# IPG_Sensor_V2.net
KiCad netlist of a schematic drawn in EasyEDA
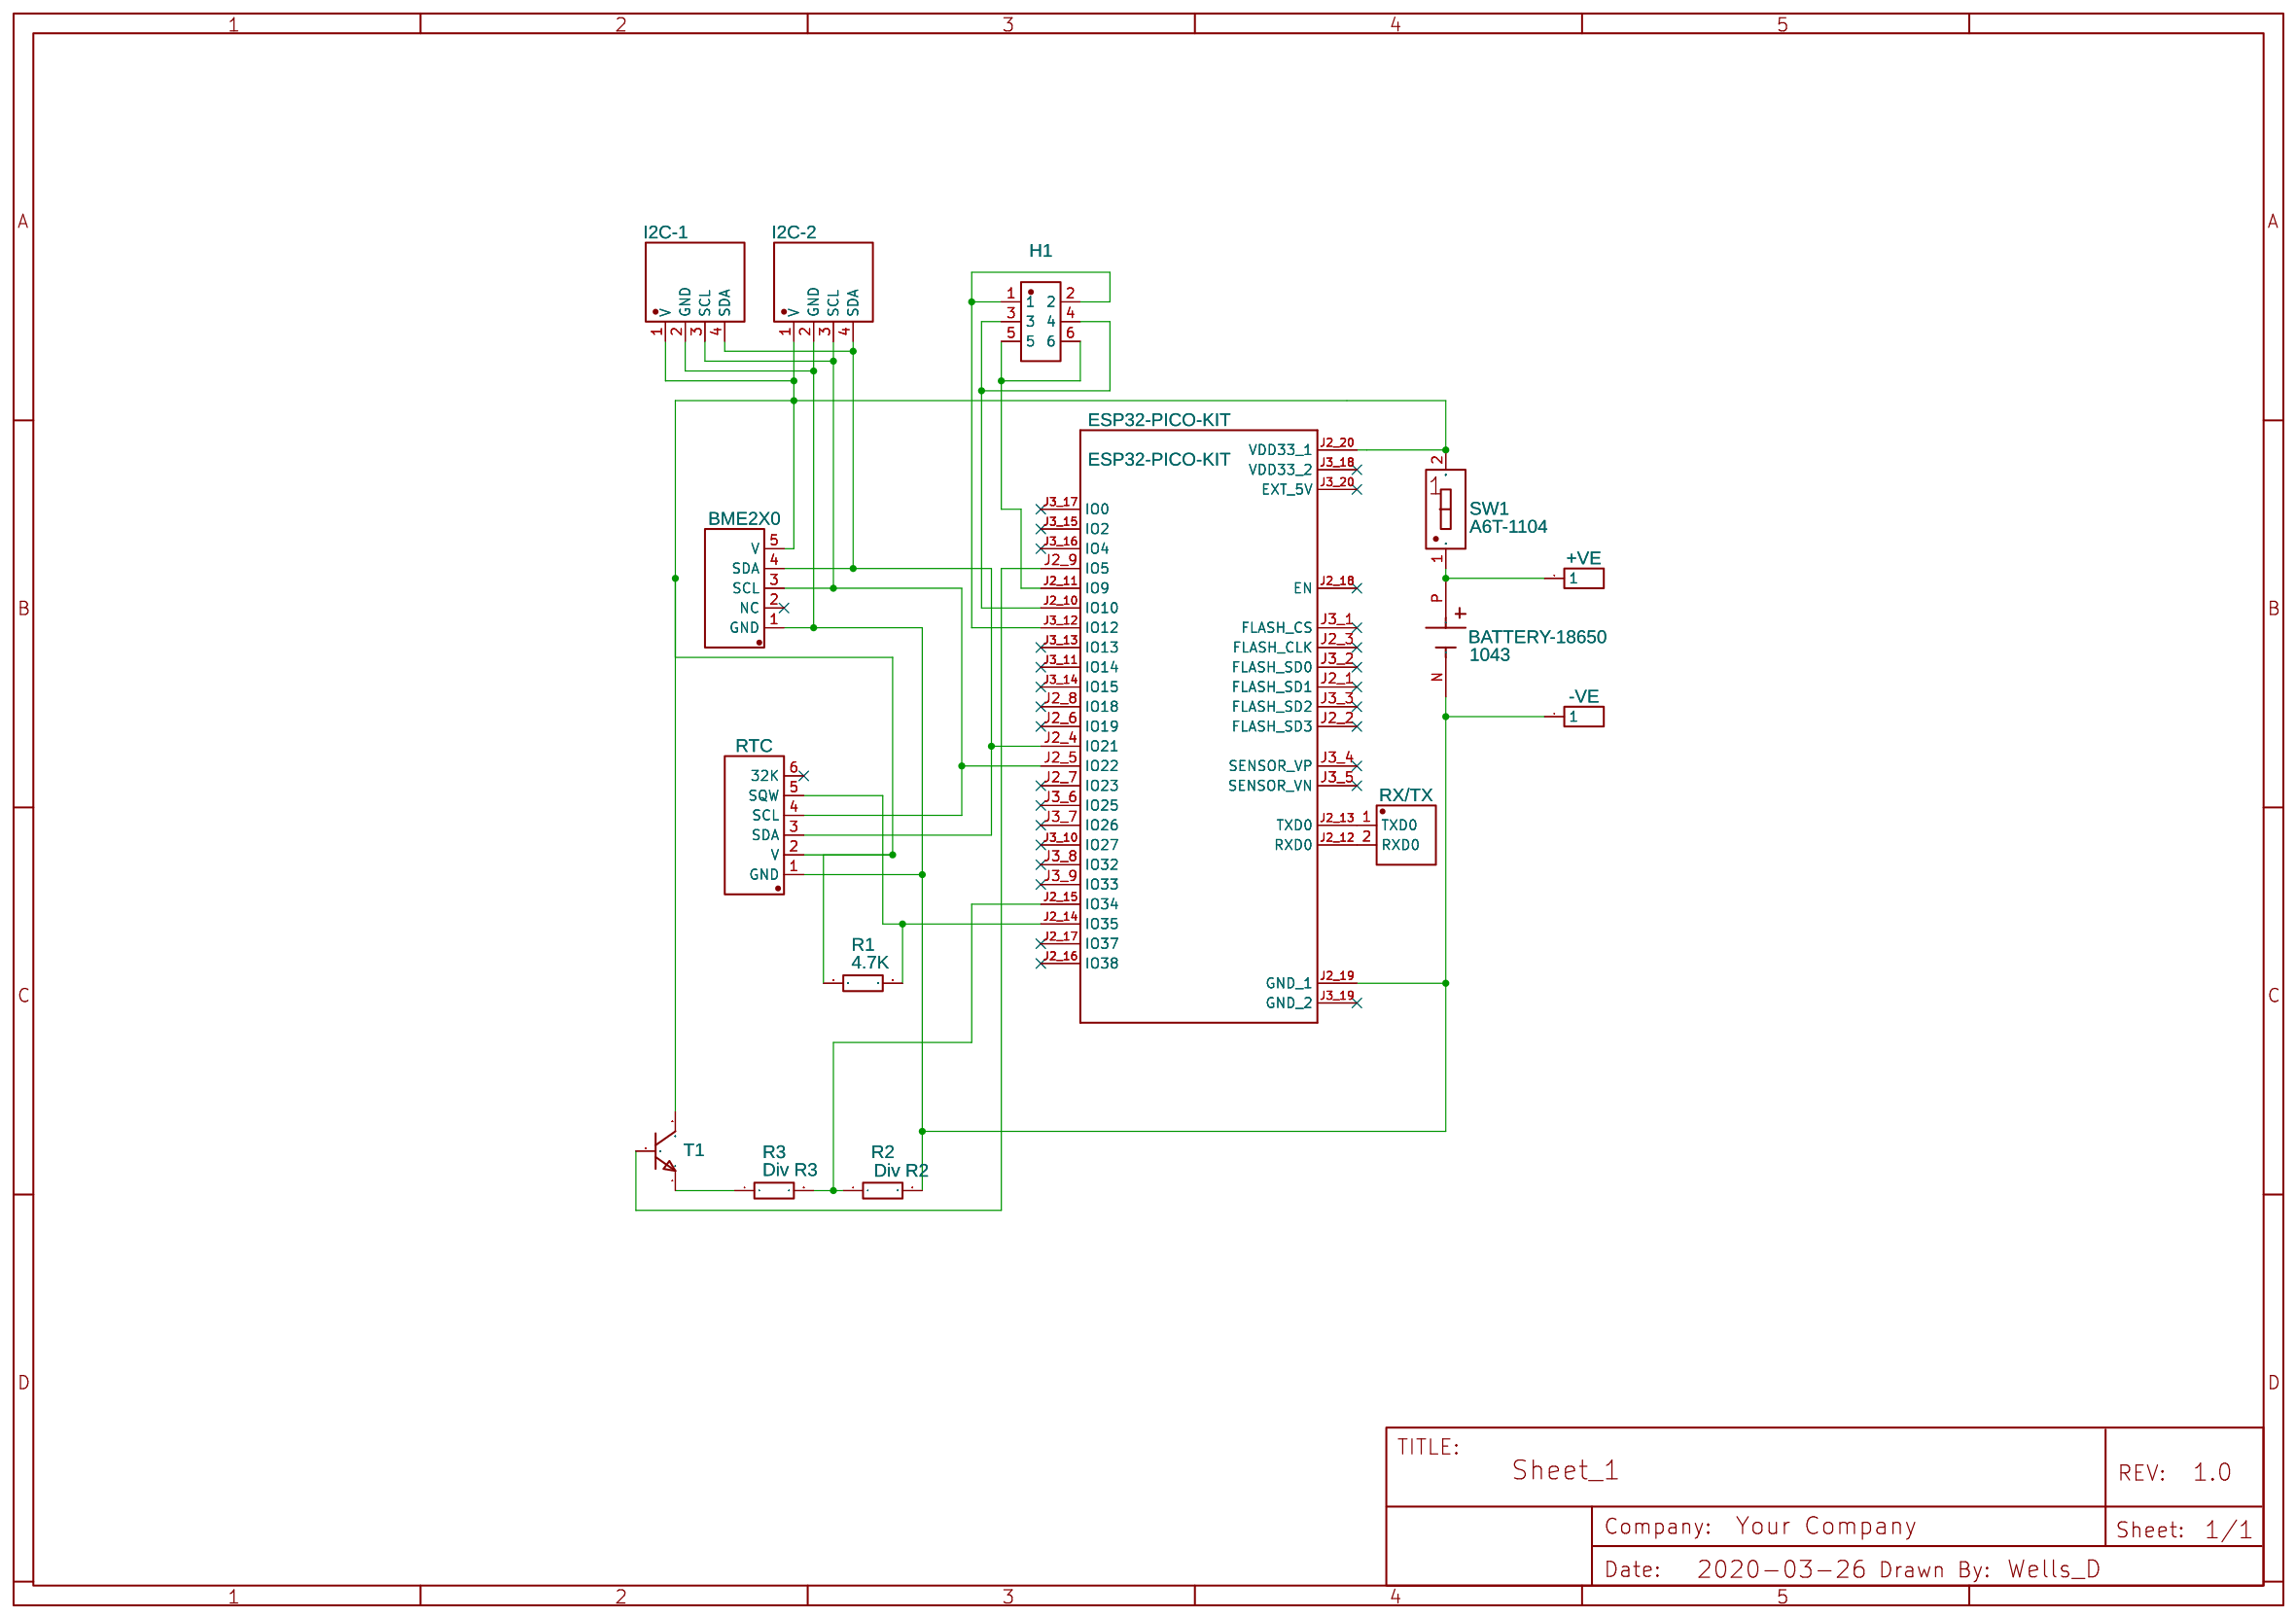
[diagram p0: schematic sheet]

(export (version "E")
  (design (tool "Eeschema 10.0.6"))
  (components
    (comp (ref "+VE")
      (value "Header-Male-2.54_1x1")
      (fields (field (name "BOM_Supplier Part") "C81276"))
      (libsource (lib "") (part "Header-Male-2.54_1x1"))
    )
    (comp (ref "-VE")
      (value "Header-Male-2.54_1x1")
      (fields (field (name "BOM_Supplier Part") "C81276"))
      (libsource (lib "") (part "Header-Male-2.54_1x1_1"))
    )
    (comp (ref "BATTERY-18650") (value "1043") (libsource (lib "") (part "1043")))
    (comp (ref "BME2X0")
      (value "2685Y-105CNG1SNA01")
      (fields (field (name "BOM_Supplier Part") "C350302"))
      (libsource (lib "") (part "2685Y-105CNG1SNA01"))
    )
    (comp (ref "ESP32-PICO-KIT") (value "ESP32-PICO-KIT") (libsource (lib "") (part "ESP32-PICO-KIT")))
    (comp (ref "H1")
      (value "67997-206HLF")
      (fields (field (name "BOM_Supplier Part") "C236051"))
      (libsource (lib "") (part "67997-206HLF"))
    )
    (comp (ref "I2C-1")
      (value "1")
      (fields (field (name "BOM_Supplier Part") "C160334"))
      (libsource (lib "") (part "RE-H042TD-1190 (LF)(SN)"))
    )
    (comp (ref "I2C-2")
      (value "2")
      (fields (field (name "BOM_Supplier Part") "C160334"))
      (libsource (lib "") (part "RE-H042TD-1190 (LF)(SN)"))
    )
    (comp (ref "R1")
      (value "4.7K")
      (fields
        (field (name "BOM_Manufacturer Part") "RN1/2W4.7KΩFT/BA1")
        (field (name "BOM_Supplier Part") "C385631")
      )
      (libsource (lib "") (part "RN1/2W4.7KΩFT/BA1"))
    )
    (comp (ref "R2")
      (value "Div R2")
      (fields
        (field (name "BOM_Manufacturer Part") "RN1/2W4.7KΩFT/BA1")
        (field (name "BOM_Supplier Part") "C385631")
      )
      (libsource (lib "") (part "RN1/2W4.7KΩFT/BA1"))
    )
    (comp (ref "R3")
      (value "Div R3")
      (fields
        (field (name "BOM_Manufacturer Part") "RN1/2W4.7KΩFT/BA1")
        (field (name "BOM_Supplier Part") "C385631")
      )
      (libsource (lib "") (part "RN1/2W4.7KΩFT/BA1"))
    )
    (comp (ref "RTC")
      (value "68000-406HLF")
      (fields (field (name "BOM_Supplier Part") "C178289"))
      (libsource (lib "") (part "68000-406HLF"))
    )
    (comp (ref "RX/TX")
      (value "RE-H022TD-1190 (LF)(SN)")
      (fields (field (name "BOM_Supplier Part") "C160332"))
      (libsource (lib "") (part "RE-H022TD-1190 (LF)(SN)"))
    )
    (comp (ref "SW1")
      (value "A6T-1104")
      (fields (field (name "BOM_Supplier Part") "C306874"))
      (libsource (lib "") (part "A6T-1104"))
    )
    (comp (ref "T1")
      (value "2N2222")
      (fields (field (name "BOM_Supplier Part") "C118536"))
      (libsource (lib "") (part "2N2222"))
    )
  )
  (nets
    (net (code "1") (name "Net-(BME2X0-GND)") (class "Default")
      (node (ref "-VE") (pin "1") (pinfunction "1_1") (pintype "input"))
      (node (ref "BATTERY-18650") (pin "N") (pinfunction "N_N") (pintype "unspecified"))
      (node (ref "BME2X0") (pin "1") (pinfunction "GND_1") (pintype "unspecified"))
      (node (ref "ESP32-PICO-KIT") (pin "J2_19") (pinfunction "GND_1_J2_19") (pintype "bidirectional"))
      (node (ref "I2C-1") (pin "2") (pinfunction "GND_2") (pintype "unspecified"))
      (node (ref "I2C-2") (pin "2") (pinfunction "GND_2") (pintype "unspecified"))
      (node (ref "R2") (pin "2") (pinfunction "2_2") (pintype "unspecified"))
      (node (ref "RTC") (pin "1") (pinfunction "GND_1") (pintype "unspecified"))
    )
    (net (code "2") (name "Net-(BME2X0-SCL)") (class "Default")
      (node (ref "BME2X0") (pin "3") (pinfunction "SCL_3") (pintype "unspecified"))
      (node (ref "ESP32-PICO-KIT") (pin "J2_5") (pinfunction "IO22_J2_5") (pintype "bidirectional"))
      (node (ref "I2C-1") (pin "3") (pinfunction "SCL_3") (pintype "unspecified"))
      (node (ref "I2C-2") (pin "3") (pinfunction "SCL_3") (pintype "unspecified"))
      (node (ref "RTC") (pin "4") (pinfunction "SCL_4") (pintype "unspecified"))
    )
    (net (code "3") (name "Net-(BME2X0-SDA)") (class "Default")
      (node (ref "BME2X0") (pin "4") (pinfunction "SDA_4") (pintype "unspecified"))
      (node (ref "ESP32-PICO-KIT") (pin "J2_4") (pinfunction "IO21_J2_4") (pintype "bidirectional"))
      (node (ref "I2C-1") (pin "4") (pinfunction "SDA_4") (pintype "unspecified"))
      (node (ref "I2C-2") (pin "4") (pinfunction "SDA_4") (pintype "unspecified"))
      (node (ref "RTC") (pin "3") (pinfunction "SDA_3") (pintype "unspecified"))
    )
    (net (code "4") (name "Net-(BME2X0-V)") (class "Default")
      (node (ref "BME2X0") (pin "5") (pinfunction "V_5") (pintype "unspecified"))
      (node (ref "ESP32-PICO-KIT") (pin "J2_20") (pinfunction "VDD33_1_J2_20") (pintype "bidirectional"))
      (node (ref "I2C-1") (pin "1") (pinfunction "V_1") (pintype "unspecified"))
      (node (ref "I2C-2") (pin "1") (pinfunction "V_1") (pintype "unspecified"))
      (node (ref "R1") (pin "1") (pinfunction "1_1") (pintype "unspecified"))
      (node (ref "RTC") (pin "2") (pinfunction "V_2") (pintype "unspecified"))
      (node (ref "SW1") (pin "2") (pinfunction "PIN2_2") (pintype "unspecified"))
      (node (ref "T1") (pin "3") (pinfunction "C_3") (pintype "unspecified"))
    )
    (net (code "5") (name "Net-(ESP32-PICO-KIT-IO5)") (class "Default")
      (node (ref "ESP32-PICO-KIT") (pin "J2_9") (pinfunction "IO5_J2_9") (pintype "bidirectional"))
      (node (ref "T1") (pin "2") (pinfunction "B_2") (pintype "unspecified"))
    )
    (net (code "6") (name "Net-(ESP32-PICO-KIT-IO9)") (class "Default")
      (node (ref "ESP32-PICO-KIT") (pin "J2_11") (pinfunction "IO9_J2_11") (pintype "bidirectional"))
      (node (ref "H1") (pin "5") (pinfunction "5_5") (pintype "unspecified"))
      (node (ref "H1") (pin "6") (pinfunction "6_6") (pintype "unspecified"))
    )
    (net (code "7") (name "Net-(ESP32-PICO-KIT-IO10)") (class "Default")
      (node (ref "ESP32-PICO-KIT") (pin "J2_10") (pinfunction "IO10_J2_10") (pintype "bidirectional"))
      (node (ref "H1") (pin "3") (pinfunction "3_3") (pintype "unspecified"))
      (node (ref "H1") (pin "4") (pinfunction "4_4") (pintype "unspecified"))
    )
    (net (code "8") (name "Net-(ESP32-PICO-KIT-IO12)") (class "Default")
      (node (ref "ESP32-PICO-KIT") (pin "J3_12") (pinfunction "IO12_J3_12") (pintype "bidirectional"))
      (node (ref "H1") (pin "1") (pinfunction "1_1") (pintype "unspecified"))
      (node (ref "H1") (pin "2") (pinfunction "2_2") (pintype "unspecified"))
    )
    (net (code "9") (name "Net-(ESP32-PICO-KIT-IO34)") (class "Default")
      (node (ref "ESP32-PICO-KIT") (pin "J2_15") (pinfunction "IO34_J2_15") (pintype "input"))
      (node (ref "R2") (pin "1") (pinfunction "1_1") (pintype "unspecified"))
      (node (ref "R3") (pin "2") (pinfunction "2_2") (pintype "unspecified"))
    )
    (net (code "10") (name "Net-(ESP32-PICO-KIT-IO35)") (class "Default")
      (node (ref "ESP32-PICO-KIT") (pin "J2_14") (pinfunction "IO35_J2_14") (pintype "input"))
      (node (ref "R1") (pin "2") (pinfunction "2_2") (pintype "unspecified"))
      (node (ref "RTC") (pin "5") (pinfunction "SQW_5") (pintype "unspecified"))
    )
    (net (code "11") (name "Net-(ESP32-PICO-KIT-RXD0)") (class "Default")
      (node (ref "ESP32-PICO-KIT") (pin "J2_12") (pinfunction "RXD0_J2_12") (pintype "bidirectional"))
      (node (ref "RX/TX") (pin "2") (pinfunction "RXD0_2") (pintype "unspecified"))
    )
    (net (code "12") (name "Net-(ESP32-PICO-KIT-TXD0)") (class "Default")
      (node (ref "ESP32-PICO-KIT") (pin "J2_13") (pinfunction "TXD0_J2_13") (pintype "bidirectional"))
      (node (ref "RX/TX") (pin "1") (pinfunction "TXD0_1") (pintype "unspecified"))
    )
    (net (code "13") (name "Net-(SW1-PIN1)") (class "Default")
      (node (ref "+VE") (pin "1") (pinfunction "1_1") (pintype "input"))
      (node (ref "BATTERY-18650") (pin "P") (pinfunction "P_P") (pintype "unspecified"))
      (node (ref "SW1") (pin "1") (pinfunction "PIN1_1") (pintype "unspecified"))
    )
    (net (code "14") (name "Net-(T1-E)") (class "Default")
      (node (ref "R3") (pin "1") (pinfunction "1_1") (pintype "unspecified"))
      (node (ref "T1") (pin "1") (pinfunction "E_1") (pintype "unspecified"))
    )
    (net (code "15") (name "unconnected-(BME2X0-NC-Pad2)") (class "Default")
      (node (ref "BME2X0") (pin "2") (pinfunction "NC_2") (pintype "unspecified+no_connect"))
    )
    (net (code "16") (name "unconnected-(ESP32-PICO-KIT-EN-PadJ2_18)") (class "Default")
      (node (ref "ESP32-PICO-KIT") (pin "J2_18") (pinfunction "EN_J2_18") (pintype "input+no_connect"))
    )
    (net (code "17") (name "unconnected-(ESP32-PICO-KIT-EXT_5V-PadJ3_20)") (class "Default")
      (node (ref "ESP32-PICO-KIT") (pin "J3_20") (pinfunction "EXT_5V_J3_20") (pintype "bidirectional+no_connect"))
    )
    (net (code "18") (name "unconnected-(ESP32-PICO-KIT-FLASH_CLK-PadJ2_3)") (class "Default")
      (node (ref "ESP32-PICO-KIT") (pin "J2_3") (pinfunction "FLASH_CLK_J2_3") (pintype "bidirectional+no_connect"))
    )
    (net (code "19") (name "unconnected-(ESP32-PICO-KIT-FLASH_CS-PadJ3_1)") (class "Default")
      (node (ref "ESP32-PICO-KIT") (pin "J3_1") (pinfunction "FLASH_CS_J3_1") (pintype "bidirectional+no_connect"))
    )
    (net (code "20") (name "unconnected-(ESP32-PICO-KIT-FLASH_SD0-PadJ3_2)") (class "Default")
      (node (ref "ESP32-PICO-KIT") (pin "J3_2") (pinfunction "FLASH_SD0_J3_2") (pintype "bidirectional+no_connect"))
    )
    (net (code "21") (name "unconnected-(ESP32-PICO-KIT-FLASH_SD1-PadJ2_1)") (class "Default")
      (node (ref "ESP32-PICO-KIT") (pin "J2_1") (pinfunction "FLASH_SD1_J2_1") (pintype "bidirectional+no_connect"))
    )
    (net (code "22") (name "unconnected-(ESP32-PICO-KIT-FLASH_SD2-PadJ3_3)") (class "Default")
      (node (ref "ESP32-PICO-KIT") (pin "J3_3") (pinfunction "FLASH_SD2_J3_3") (pintype "bidirectional+no_connect"))
    )
    (net (code "23") (name "unconnected-(ESP32-PICO-KIT-FLASH_SD3-PadJ2_2)") (class "Default")
      (node (ref "ESP32-PICO-KIT") (pin "J2_2") (pinfunction "FLASH_SD3_J2_2") (pintype "bidirectional+no_connect"))
    )
    (net (code "24") (name "unconnected-(ESP32-PICO-KIT-GND_2-PadJ3_19)") (class "Default")
      (node (ref "ESP32-PICO-KIT") (pin "J3_19") (pinfunction "GND_2_J3_19") (pintype "bidirectional+no_connect"))
    )
    (net (code "25") (name "unconnected-(ESP32-PICO-KIT-IO0-PadJ3_17)") (class "Default")
      (node (ref "ESP32-PICO-KIT") (pin "J3_17") (pinfunction "IO0_J3_17") (pintype "bidirectional+no_connect"))
    )
    (net (code "26") (name "unconnected-(ESP32-PICO-KIT-IO2-PadJ3_15)") (class "Default")
      (node (ref "ESP32-PICO-KIT") (pin "J3_15") (pinfunction "IO2_J3_15") (pintype "bidirectional+no_connect"))
    )
    (net (code "27") (name "unconnected-(ESP32-PICO-KIT-IO4-PadJ3_16)") (class "Default")
      (node (ref "ESP32-PICO-KIT") (pin "J3_16") (pinfunction "IO4_J3_16") (pintype "bidirectional+no_connect"))
    )
    (net (code "28") (name "unconnected-(ESP32-PICO-KIT-IO13-PadJ3_13)") (class "Default")
      (node (ref "ESP32-PICO-KIT") (pin "J3_13") (pinfunction "IO13_J3_13") (pintype "bidirectional+no_connect"))
    )
    (net (code "29") (name "unconnected-(ESP32-PICO-KIT-IO14-PadJ3_11)") (class "Default")
      (node (ref "ESP32-PICO-KIT") (pin "J3_11") (pinfunction "IO14_J3_11") (pintype "bidirectional+no_connect"))
    )
    (net (code "30") (name "unconnected-(ESP32-PICO-KIT-IO15-PadJ3_14)") (class "Default")
      (node (ref "ESP32-PICO-KIT") (pin "J3_14") (pinfunction "IO15_J3_14") (pintype "bidirectional+no_connect"))
    )
    (net (code "31") (name "unconnected-(ESP32-PICO-KIT-IO18-PadJ2_8)") (class "Default")
      (node (ref "ESP32-PICO-KIT") (pin "J2_8") (pinfunction "IO18_J2_8") (pintype "bidirectional+no_connect"))
    )
    (net (code "32") (name "unconnected-(ESP32-PICO-KIT-IO19-PadJ2_6)") (class "Default")
      (node (ref "ESP32-PICO-KIT") (pin "J2_6") (pinfunction "IO19_J2_6") (pintype "bidirectional+no_connect"))
    )
    (net (code "33") (name "unconnected-(ESP32-PICO-KIT-IO23-PadJ2_7)") (class "Default")
      (node (ref "ESP32-PICO-KIT") (pin "J2_7") (pinfunction "IO23_J2_7") (pintype "bidirectional+no_connect"))
    )
    (net (code "34") (name "unconnected-(ESP32-PICO-KIT-IO25-PadJ3_6)") (class "Default")
      (node (ref "ESP32-PICO-KIT") (pin "J3_6") (pinfunction "IO25_J3_6") (pintype "bidirectional+no_connect"))
    )
    (net (code "35") (name "unconnected-(ESP32-PICO-KIT-IO26-PadJ3_7)") (class "Default")
      (node (ref "ESP32-PICO-KIT") (pin "J3_7") (pinfunction "IO26_J3_7") (pintype "bidirectional+no_connect"))
    )
    (net (code "36") (name "unconnected-(ESP32-PICO-KIT-IO27-PadJ3_10)") (class "Default")
      (node (ref "ESP32-PICO-KIT") (pin "J3_10") (pinfunction "IO27_J3_10") (pintype "bidirectional+no_connect"))
    )
    (net (code "37") (name "unconnected-(ESP32-PICO-KIT-IO32-PadJ3_8)") (class "Default")
      (node (ref "ESP32-PICO-KIT") (pin "J3_8") (pinfunction "IO32_J3_8") (pintype "bidirectional+no_connect"))
    )
    (net (code "38") (name "unconnected-(ESP32-PICO-KIT-IO33-PadJ3_9)") (class "Default")
      (node (ref "ESP32-PICO-KIT") (pin "J3_9") (pinfunction "IO33_J3_9") (pintype "bidirectional+no_connect"))
    )
    (net (code "39") (name "unconnected-(ESP32-PICO-KIT-IO37-PadJ2_17)") (class "Default")
      (node (ref "ESP32-PICO-KIT") (pin "J2_17") (pinfunction "IO37_J2_17") (pintype "input+no_connect"))
    )
    (net (code "40") (name "unconnected-(ESP32-PICO-KIT-IO38-PadJ2_16)") (class "Default")
      (node (ref "ESP32-PICO-KIT") (pin "J2_16") (pinfunction "IO38_J2_16") (pintype "input+no_connect"))
    )
    (net (code "41") (name "unconnected-(ESP32-PICO-KIT-SENSOR_VN-PadJ3_5)") (class "Default")
      (node (ref "ESP32-PICO-KIT") (pin "J3_5") (pinfunction "SENSOR_VN_J3_5") (pintype "input+no_connect"))
    )
    (net (code "42") (name "unconnected-(ESP32-PICO-KIT-SENSOR_VP-PadJ3_4)") (class "Default")
      (node (ref "ESP32-PICO-KIT") (pin "J3_4") (pinfunction "SENSOR_VP_J3_4") (pintype "input+no_connect"))
    )
    (net (code "43") (name "unconnected-(ESP32-PICO-KIT-VDD33_2-PadJ3_18)") (class "Default")
      (node (ref "ESP32-PICO-KIT") (pin "J3_18") (pinfunction "VDD33_2_J3_18") (pintype "bidirectional+no_connect"))
    )
    (net (code "44") (name "unconnected-(RTC-32K-Pad6)") (class "Default")
      (node (ref "RTC") (pin "6") (pinfunction "32K_6") (pintype "unspecified+no_connect"))
    )
  )
)
